# 04_Power_Supplies.net
KiCad netlist of a schematic drawn in Altium Designer
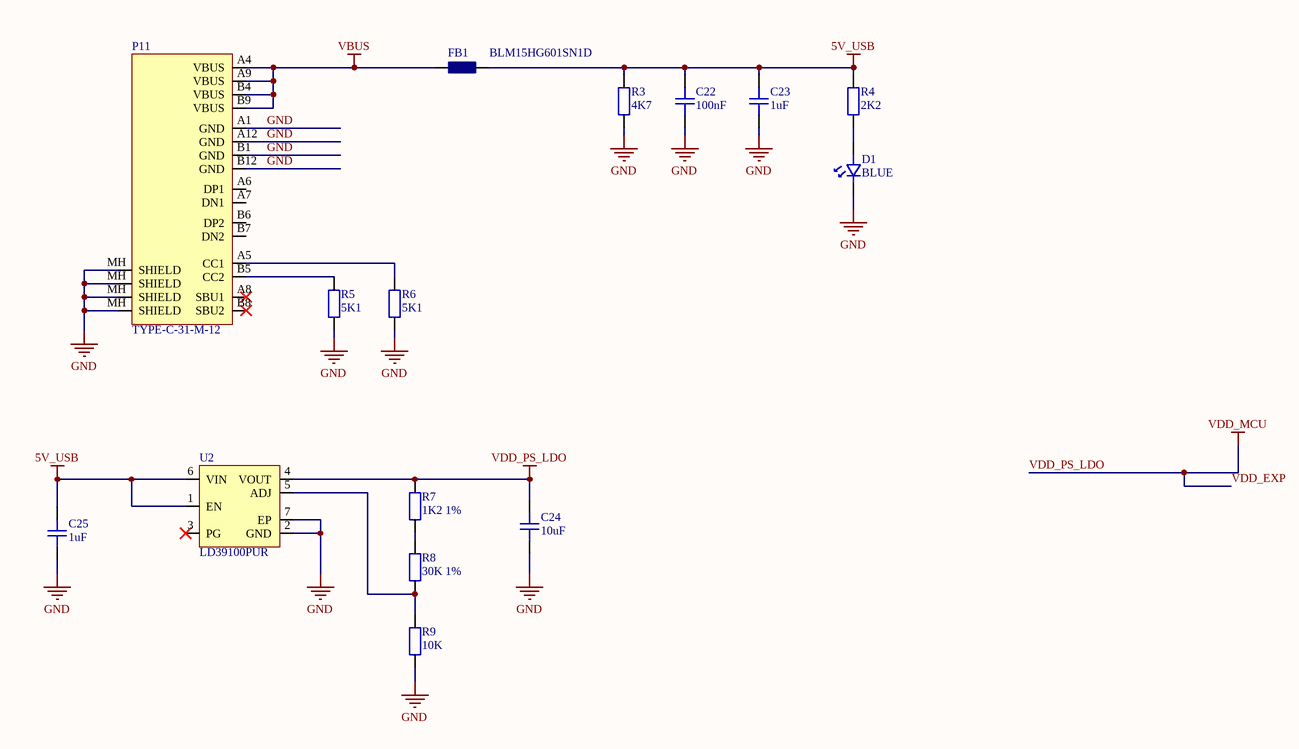
[diagram p0: [04]Power Supplies.SchDoc]

(export (version "E")
  (design (tool "Eeschema 10.0.6"))
  (components
    (comp (ref "C22")
      (value "100nF")
      (footprint "CAPC1005L")
      (description "Surface Mount Unpolarized Capacitor")
      (libsource (lib "Discrete") (part "CAP_CHP"))
    )
    (comp (ref "C23")
      (value "1uF")
      (footprint "CAPC1005L")
      (description "Surface Mount Unpolarized Capacitor")
      (libsource (lib "Discrete") (part "CAP_CHP"))
    )
    (comp (ref "C24")
      (value "10uF")
      (footprint "CAPC1608N")
      (description "Surface Mount Unpolarized Capacitor")
      (libsource (lib "Discrete") (part "CAP_CHP"))
    )
    (comp (ref "C25")
      (value "1uF")
      (footprint "CAPC1005L")
      (description "Surface Mount Unpolarized Capacitor")
      (libsource (lib "Discrete") (part "CAP_CHP"))
    )
    (comp (ref "D1")
      (value "BLUE")
      (footprint "LEDC1608L")
      (description "Surface Mount LED")
      (libsource (lib "Discrete") (part "LED_SMD"))
    )
    (comp (ref "FB1")
      (value "BLM15HG601SN1D")
      (footprint "FBDC1005L")
      (description "Surface Mount Ferrite Bead")
      (libsource (lib "Discrete") (part "FBD_CHP"))
    )
    (comp (ref "P11")
      (value "TYPE-C-31-M-12")
      (footprint "TYPE-C-31-M-12")
      (description "USB Type-C Connector")
      (libsource (lib "Connector") (part "TYPE-C-31-M-12"))
    )
    (comp (ref "R3")
      (value "4K7")
      (footprint "RESC1005L")
      (description "Surface Mount Resistor")
      (libsource (lib "Discrete") (part "RES_CHP"))
    )
    (comp (ref "R4")
      (value "2K2")
      (footprint "RESC1005L")
      (description "Surface Mount Resistor")
      (libsource (lib "Discrete") (part "RES_CHP"))
    )
    (comp (ref "R5")
      (value "5K1")
      (footprint "RESC1005L")
      (description "Surface Mount Resistor")
      (libsource (lib "Discrete") (part "RES_CHP"))
    )
    (comp (ref "R6")
      (value "5K1")
      (footprint "RESC1005L")
      (description "Surface Mount Resistor")
      (libsource (lib "Discrete") (part "RES_CHP"))
    )
    (comp (ref "R7")
      (value "1K2 1%")
      (footprint "RESC1005L")
      (description "Surface Mount Resistor")
      (libsource (lib "Discrete") (part "RES_CHP"))
    )
    (comp (ref "R8")
      (value "30K 1%")
      (footprint "RESC1005L")
      (description "Surface Mount Resistor")
      (libsource (lib "Discrete") (part "RES_CHP"))
    )
    (comp (ref "R9")
      (value "10K")
      (footprint "RESC1005L")
      (description "Surface Mount Resistor")
      (libsource (lib "Discrete") (part "RES_CHP"))
    )
    (comp (ref "U2")
      (value "LD39100PUR")
      (footprint "DFN6")
      (description "Voltage Regulator, 1A, Low Quiescent Current  ,DFN6 Tape&Reel")
      (libsource (lib "IC") (part "LD39100PUR"))
    )
  )
  (nets
    (net (code "1") (name "5V_USB") (class "Default")
      (node (ref "C22") (pin "2") (pinfunction "2_2") (pintype "passive"))
      (node (ref "C23") (pin "2") (pinfunction "2_2") (pintype "passive"))
      (node (ref "C25") (pin "2") (pinfunction "2_2") (pintype "passive"))
      (node (ref "FB1") (pin "2") (pinfunction "2_2") (pintype "passive"))
      (node (ref "R3") (pin "2") (pinfunction "2_2") (pintype "passive"))
      (node (ref "R4") (pin "1") (pinfunction "1_1") (pintype "passive"))
      (node (ref "U2") (pin "1") (pinfunction "EN_1") (pintype "passive"))
      (node (ref "U2") (pin "6") (pinfunction "VIN_6") (pintype "passive"))
    )
    (net (code "2") (name "GND") (class "Default")
      (node (ref "C22") (pin "1") (pinfunction "1_1") (pintype "passive"))
      (node (ref "C23") (pin "1") (pinfunction "1_1") (pintype "passive"))
      (node (ref "C24") (pin "1") (pinfunction "1_1") (pintype "passive"))
      (node (ref "C25") (pin "1") (pinfunction "1_1") (pintype "passive"))
      (node (ref "D1") (pin "1") (pinfunction "1_1") (pintype "passive"))
      (node (ref "P11") (pin "A1") (pinfunction "GND_A1") (pintype "passive"))
      (node (ref "P11") (pin "A12") (pinfunction "GND_A12") (pintype "passive"))
      (node (ref "P11") (pin "B1") (pinfunction "GND_B1") (pintype "passive"))
      (node (ref "P11") (pin "B12") (pinfunction "GND_B12") (pintype "passive"))
      (node (ref "P11") (pin "MH") (pinfunction "SHIELD_MH") (pintype "passive"))
      (node (ref "R3") (pin "1") (pinfunction "1_1") (pintype "passive"))
      (node (ref "R5") (pin "1") (pinfunction "1_1") (pintype "passive"))
      (node (ref "R6") (pin "1") (pinfunction "1_1") (pintype "passive"))
      (node (ref "R9") (pin "1") (pinfunction "1_1") (pintype "passive"))
      (node (ref "U2") (pin "2") (pinfunction "GND_2") (pintype "passive"))
      (node (ref "U2") (pin "7") (pinfunction "EP_7") (pintype "passive"))
    )
    (net (code "3") (name "Net-(D1-Pad2)") (class "Default")
      (node (ref "D1") (pin "2") (pinfunction "2_2") (pintype "passive"))
      (node (ref "R4") (pin "2") (pinfunction "2_2") (pintype "passive"))
    )
    (net (code "4") (name "Net-(P11-CC1)") (class "Default")
      (node (ref "P11") (pin "A5") (pinfunction "CC1_A5") (pintype "passive"))
      (node (ref "R6") (pin "2") (pinfunction "2_2") (pintype "passive"))
    )
    (net (code "5") (name "Net-(P11-CC2)") (class "Default")
      (node (ref "P11") (pin "B5") (pinfunction "CC2_B5") (pintype "passive"))
      (node (ref "R5") (pin "2") (pinfunction "2_2") (pintype "passive"))
    )
    (net (code "6") (name "Net-(R7-Pad1)") (class "Default")
      (node (ref "R7") (pin "1") (pinfunction "1_1") (pintype "passive"))
      (node (ref "R8") (pin "2") (pinfunction "2_2") (pintype "passive"))
    )
    (net (code "7") (name "Net-(U2-ADJ)") (class "Default")
      (node (ref "R8") (pin "1") (pinfunction "1_1") (pintype "passive"))
      (node (ref "R9") (pin "2") (pinfunction "2_2") (pintype "passive"))
      (node (ref "U2") (pin "5") (pinfunction "ADJ_5") (pintype "passive"))
    )
    (net (code "8") (name "VBUS") (class "Default")
      (node (ref "FB1") (pin "1") (pinfunction "1_1") (pintype "passive"))
      (node (ref "P11") (pin "A4") (pinfunction "VBUS_A4") (pintype "passive"))
      (node (ref "P11") (pin "A9") (pinfunction "VBUS_A9") (pintype "passive"))
      (node (ref "P11") (pin "B4") (pinfunction "VBUS_B4") (pintype "passive"))
      (node (ref "P11") (pin "B9") (pinfunction "VBUS_B9") (pintype "passive"))
    )
    (net (code "9") (name "VDD_MCU") (class "Default")
      (node (ref "C24") (pin "2") (pinfunction "2_2") (pintype "passive"))
      (node (ref "R7") (pin "2") (pinfunction "2_2") (pintype "passive"))
      (node (ref "U2") (pin "4") (pinfunction "VOUT_4") (pintype "passive"))
    )
    (net (code "10") (name "unconnected-(P11-DN1-PadA7)") (class "Default")
      (node (ref "P11") (pin "A7") (pinfunction "DN1_A7") (pintype "passive"))
    )
    (net (code "11") (name "unconnected-(P11-DN2-PadB7)") (class "Default")
      (node (ref "P11") (pin "B7") (pinfunction "DN2_B7") (pintype "passive"))
    )
    (net (code "12") (name "unconnected-(P11-DP1-PadA6)") (class "Default")
      (node (ref "P11") (pin "A6") (pinfunction "DP1_A6") (pintype "passive"))
    )
    (net (code "13") (name "unconnected-(P11-DP2-PadB6)") (class "Default")
      (node (ref "P11") (pin "B6") (pinfunction "DP2_B6") (pintype "passive"))
    )
    (net (code "14") (name "unconnected-(P11-SBU1-PadA8)") (class "Default")
      (node (ref "P11") (pin "A8") (pinfunction "SBU1_A8") (pintype "passive+no_connect"))
    )
    (net (code "15") (name "unconnected-(P11-SBU2-PadB8)") (class "Default")
      (node (ref "P11") (pin "B8") (pinfunction "SBU2_B8") (pintype "passive+no_connect"))
    )
    (net (code "16") (name "unconnected-(U2-PG-Pad3)") (class "Default")
      (node (ref "U2") (pin "3") (pinfunction "PG_3") (pintype "passive+no_connect"))
    )
  )
)
